# DC-DC.net
KiCad netlist of a schematic drawn in EAGLE
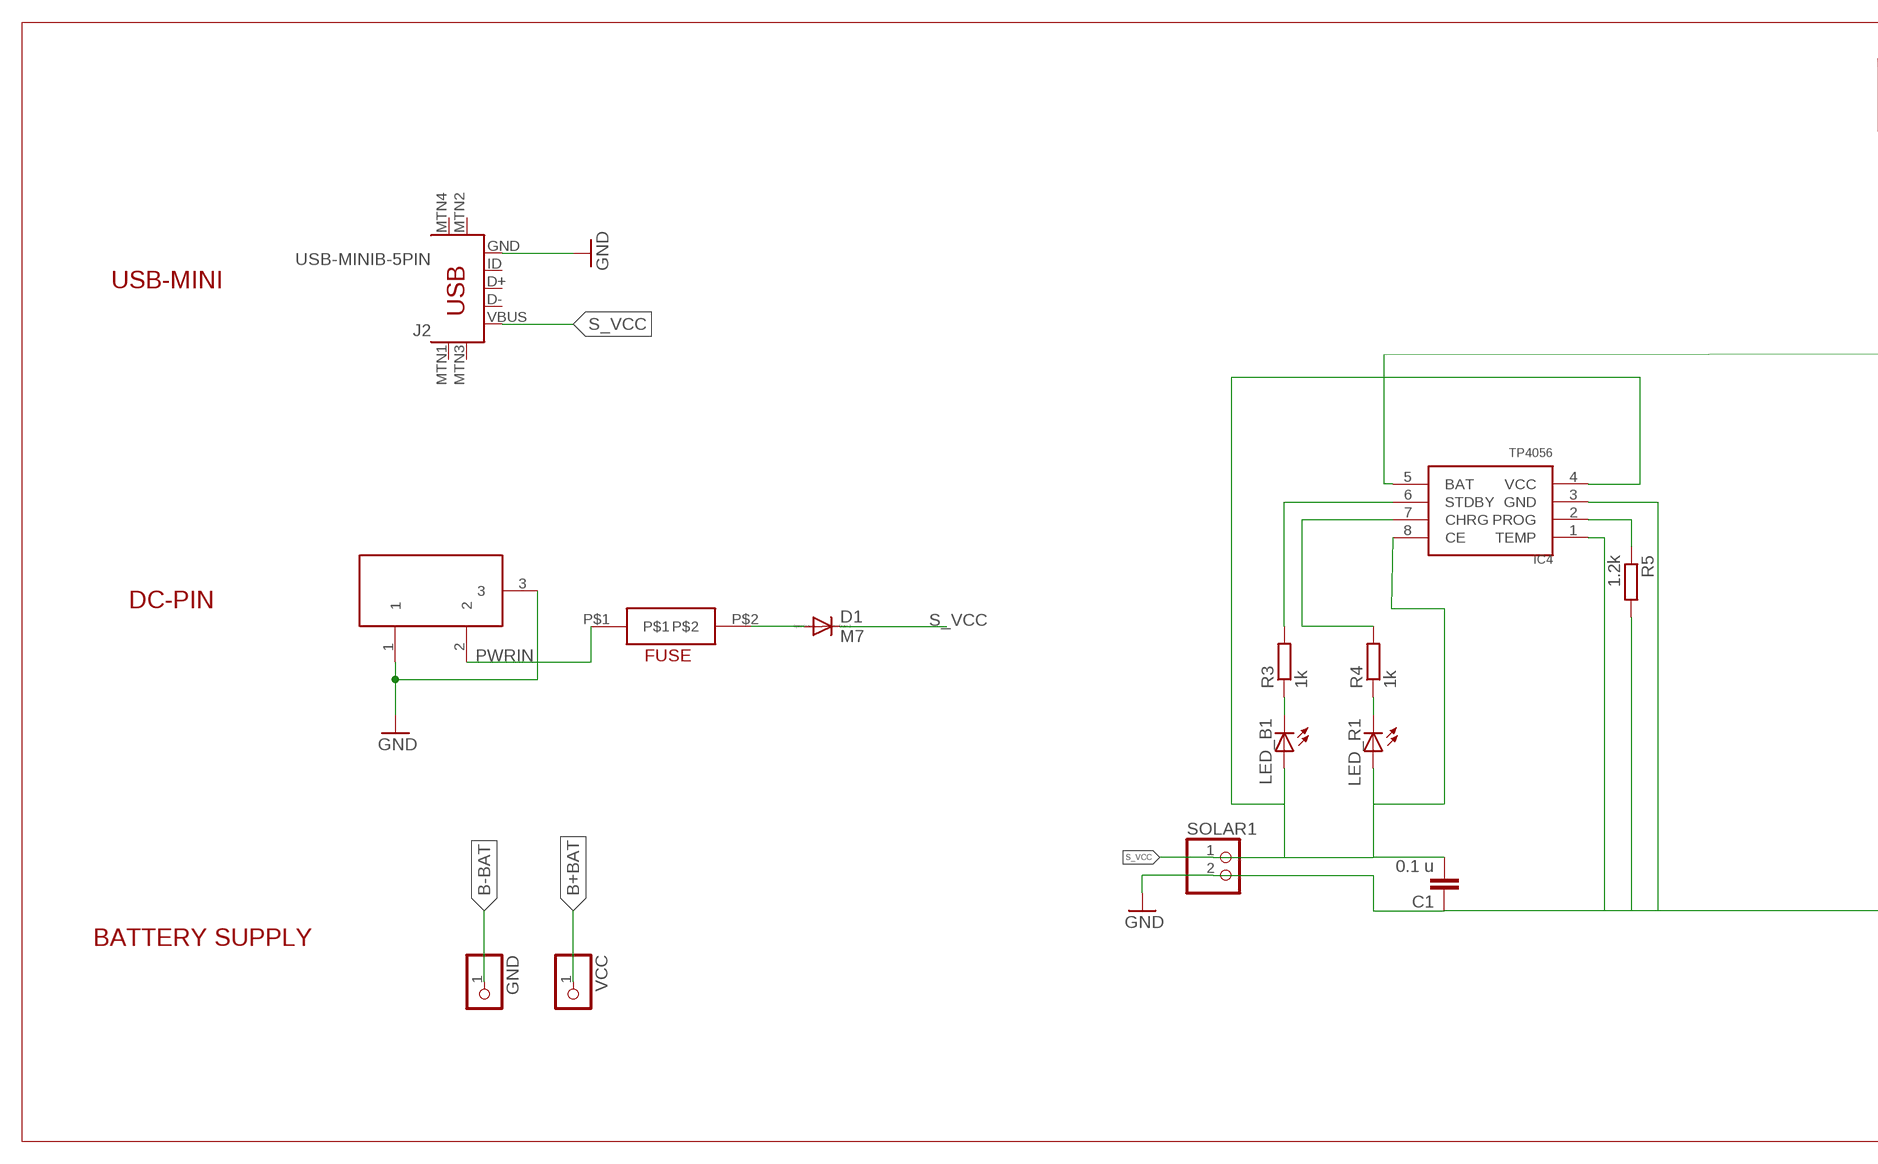
[diagram p0: schematic, sheet 1, part 1 of 2]
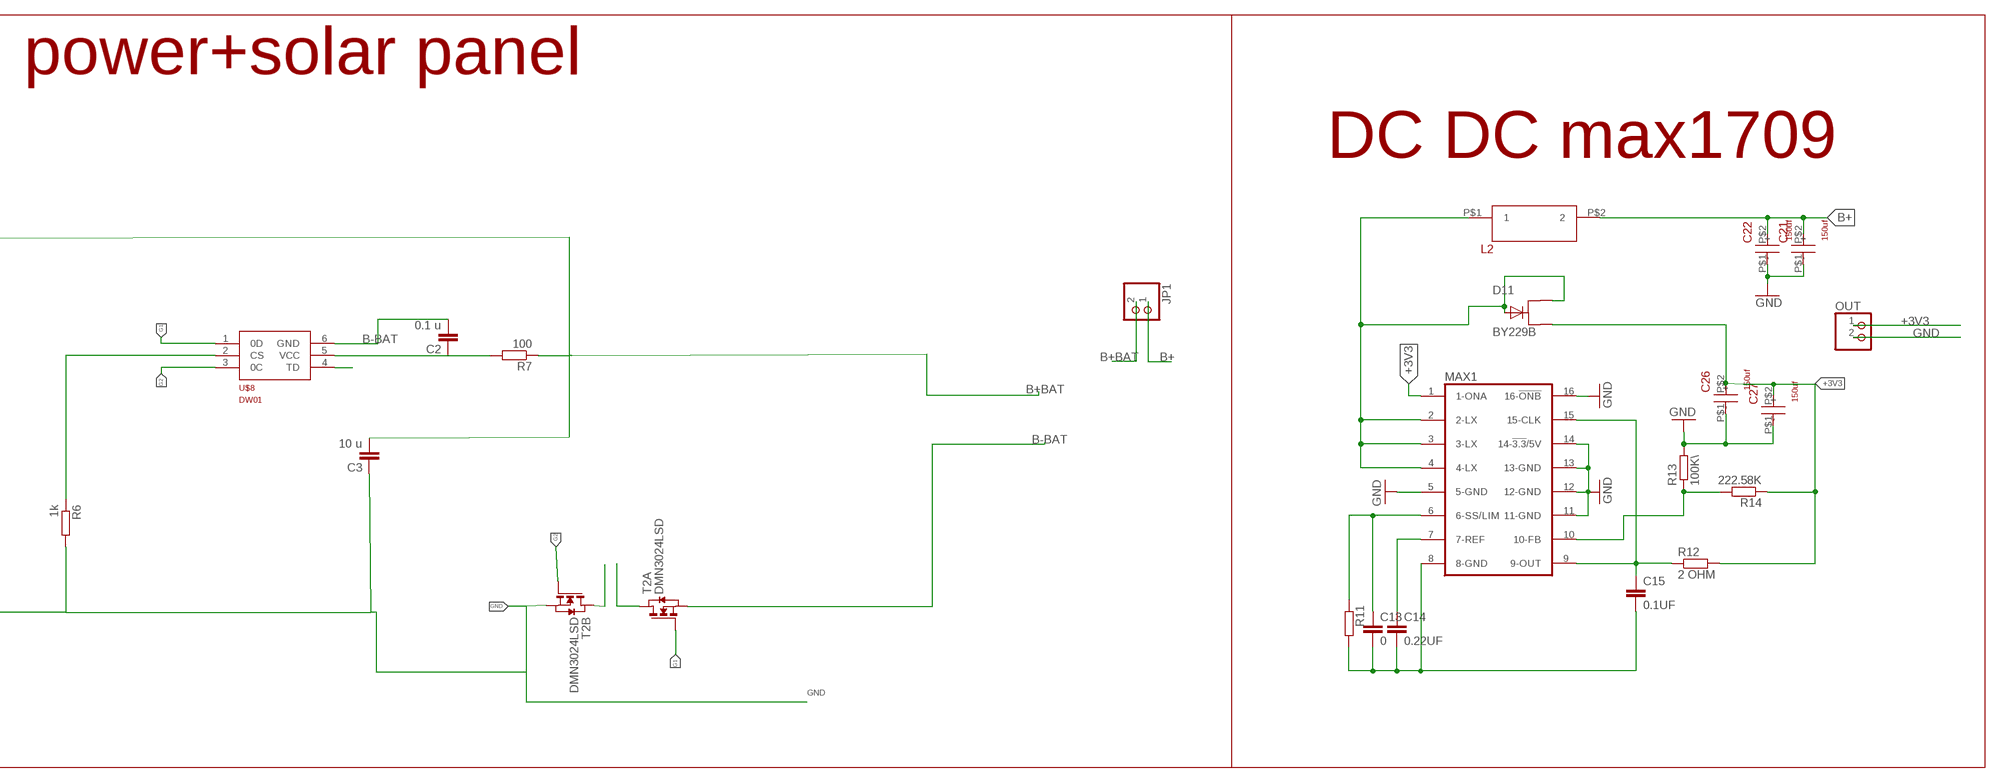
[diagram p1: schematic, sheet 1, part 2 of 2]

(export (version "E")
  (design (tool "Eeschema 10.0.6"))
  (components
    (comp (ref "C1")
      (value "0.1 u")
      (footprint "eagle-import:C0805")
      (libsource (lib "eagle-import") (part "C-EUC0805"))
    )
    (comp (ref "C2")
      (value "0.1 u")
      (footprint "eagle-import:C0805")
      (libsource (lib "eagle-import") (part "C-EUC0805"))
    )
    (comp (ref "C3")
      (value "10 u")
      (footprint "eagle-import:C0805")
      (libsource (lib "eagle-import") (part "C-EUC0805"))
    )
    (comp (ref "C13")
      (value "0")
      (footprint "eagle-import:C0805")
      (libsource (lib "eagle-import") (part "C-EUC0805"))
    )
    (comp (ref "C14")
      (value "0.22UF")
      (footprint "eagle-import:C0805")
      (libsource (lib "eagle-import") (part "C-EUC0805"))
    )
    (comp (ref "C15")
      (value "0.1UF")
      (footprint "eagle-import:C0805")
      (libsource (lib "eagle-import") (part "C-EUC0805"))
    )
    (comp (ref "C21")
      (value "150uf")
      (footprint "eagle-import:CAP")
      (libsource (lib "eagle-import") (part "MOSHE_CAP"))
    )
    (comp (ref "C22")
      (value "150uf")
      (footprint "eagle-import:CAP")
      (libsource (lib "eagle-import") (part "MOSHE_CAP"))
    )
    (comp (ref "C26")
      (value "150uf")
      (footprint "eagle-import:CAP")
      (libsource (lib "eagle-import") (part "MOSHE_CAP"))
    )
    (comp (ref "C27")
      (value "150uf")
      (footprint "eagle-import:CAP")
      (libsource (lib "eagle-import") (part "MOSHE_CAP"))
    )
    (comp (ref "D1")
      (value "M7")
      (footprint "eagle-import:SMB")
      (libsource (lib "eagle-import") (part "DIODE-SMB"))
    )
    (comp (ref "D11")
      (value "BY229B")
      (footprint "eagle-import:TO263AB")
      (libsource (lib "eagle-import") (part "BY229B"))
    )
    (comp (ref "GND")
      (value "PINHD-1X1")
      (footprint "eagle-import:1X01")
      (libsource (lib "eagle-import") (part "PINHD-1X1"))
    )
    (comp (ref "IC4")
      (value "TP4056")
      (footprint "eagle-import:SOP-8")
      (libsource (lib "eagle-import") (part "TP4056"))
    )
    (comp (ref "J2")
      (value "USB-MINIB-5PIN")
      (footprint "eagle-import:USB-MINIB")
      (libsource (lib "eagle-import") (part "USB-MINIB-5PIN"))
    )
    (comp (ref "JP1")
      (value "PINHD-1X2")
      (footprint "eagle-import:1X02")
      (libsource (lib "eagle-import") (part "PINHD-1X2"))
    )
    (comp (ref "L2")
      (value "INDUCTOR")
      (footprint "eagle-import:INDUCTOR_150")
      (libsource (lib "eagle-import") (part "INDUCTOR"))
    )
    (comp (ref "LED_B1")
      (value "LEDCHIP-LED0805")
      (footprint "eagle-import:CHIP-LED0805")
      (libsource (lib "eagle-import") (part "LEDCHIP-LED0805"))
    )
    (comp (ref "LED_R1")
      (value "LEDCHIP-LED0805")
      (footprint "eagle-import:CHIP-LED0805")
      (libsource (lib "eagle-import") (part "LEDCHIP-LED0805"))
    )
    (comp (ref "MAX1")
      (value "MOSHE_MAX1709F")
      (footprint "eagle-import:MAX1709")
      (libsource (lib "eagle-import") (part "MOSHE_MAX1709F"))
    )
    (comp (ref "OUT")
      (value "PINHD-1X2")
      (footprint "eagle-import:1X02")
      (libsource (lib "eagle-import") (part "PINHD-1X2"))
    )
    (comp (ref "R3")
      (value "1k")
      (footprint "eagle-import:R0805")
      (libsource (lib "eagle-import") (part "R-EU_R0805"))
    )
    (comp (ref "R4")
      (value "1k")
      (footprint "eagle-import:R0805")
      (libsource (lib "eagle-import") (part "R-EU_R0805"))
    )
    (comp (ref "R5")
      (value "1.2k")
      (footprint "eagle-import:R0805")
      (libsource (lib "eagle-import") (part "R-EU_R0805"))
    )
    (comp (ref "R6")
      (value "1k")
      (footprint "eagle-import:R0805")
      (libsource (lib "eagle-import") (part "R-EU_R0805"))
    )
    (comp (ref "R7")
      (value "100")
      (footprint "eagle-import:R0805")
      (libsource (lib "eagle-import") (part "R-EU_R0805"))
    )
    (comp (ref "R11")
      (value "R-EU_R0805")
      (footprint "eagle-import:R0805")
      (libsource (lib "eagle-import") (part "R-EU_R0805"))
    )
    (comp (ref "R12")
      (value "2 OHM")
      (footprint "eagle-import:R0805")
      (libsource (lib "eagle-import") (part "R-EU_R0805"))
    )
    (comp (ref "R13")
      (value "100K\\")
      (footprint "eagle-import:R0805")
      (libsource (lib "eagle-import") (part "R-EU_R0805"))
    )
    (comp (ref "R14")
      (value "222.58K")
      (footprint "eagle-import:R0805")
      (libsource (lib "eagle-import") (part "R-EU_R0805"))
    )
    (comp (ref "SOLAR1")
      (value "PINHD-1X2")
      (footprint "eagle-import:1X02")
      (libsource (lib "eagle-import") (part "PINHD-1X2"))
    )
    (comp (ref "T2")
      (value "DMN3024LSD")
      (footprint "eagle-import:TSSOP-8")
      (libsource (lib "eagle-import") (part "DMN3024LSD"))
    )
    (comp (ref "U$5")
      (value "FUSE_M")
      (footprint "eagle-import:DIP2")
      (libsource (lib "eagle-import") (part "FUSE_M"))
    )
    (comp (ref "U$8")
      (value "DW01")
      (footprint "eagle-import:SOT23-6")
      (libsource (lib "eagle-import") (part "DW01"))
    )
    (comp (ref "VCC")
      (value "PINHD-1X1")
      (footprint "eagle-import:1X01")
      (libsource (lib "eagle-import") (part "PINHD-1X1"))
    )
    (comp (ref "X1")
      (value "DC21MMX")
      (footprint "eagle-import:DC-21MM")
      (libsource (lib "eagle-import") (part "DC21MMX"))
    )
  )
  (nets
    (net (code "1") (name "+3V3") (class "Default")
      (node (ref "C26") (pin "P$2") (pinfunction "-_P$2") (pintype "bidirectional"))
      (node (ref "C27") (pin "P$2") (pinfunction "-_P$2") (pintype "bidirectional"))
      (node (ref "D11") (pin "K") (pinfunction "K_K") (pintype "passive"))
      (node (ref "MAX1") (pin "1") (pinfunction "1-ONA_1") (pintype "passive"))
      (node (ref "OUT") (pin "1") (pinfunction "1_1") (pintype "passive"))
      (node (ref "R12") (pin "2") (pinfunction "2_2") (pintype "passive"))
      (node (ref "R14") (pin "1") (pinfunction "1_1") (pintype "passive"))
    )
    (net (code "2") (name "/PWRIN") (class "Default")
      (node (ref "U$5") (pin "P$1") (pinfunction "P$1_P$1") (pintype "bidirectional"))
      (node (ref "X1") (pin "2") (pinfunction "2_2") (pintype "power_in"))
    )
    (net (code "3") (name "B+") (class "Default")
      (node (ref "C21") (pin "P$2") (pinfunction "-_P$2") (pintype "bidirectional"))
      (node (ref "C22") (pin "P$2") (pinfunction "-_P$2") (pintype "bidirectional"))
      (node (ref "JP1") (pin "1") (pinfunction "1_1") (pintype "passive"))
      (node (ref "L2") (pin "P$2") (pinfunction "2_P$2") (pintype "bidirectional"))
    )
    (net (code "4") (name "B+BAT") (class "Default")
      (node (ref "C3") (pin "2") (pinfunction "2_2") (pintype "passive"))
      (node (ref "IC4") (pin "5") (pinfunction "BAT_5") (pintype "bidirectional"))
      (node (ref "JP1") (pin "2") (pinfunction "2_2") (pintype "passive"))
      (node (ref "R7") (pin "1") (pinfunction "1_1") (pintype "passive"))
      (node (ref "VCC") (pin "1") (pinfunction "1_1") (pintype "passive"))
    )
    (net (code "5") (name "B-BAT") (class "Default")
      (node (ref "C2") (pin "2") (pinfunction "2_2") (pintype "passive"))
      (node (ref "GND") (pin "1") (pinfunction "1_1") (pintype "passive"))
      (node (ref "T2") (pin "2") (pinfunction "S_2") (pintype "passive"))
      (node (ref "T2") (pin "3") (pinfunction "S_3") (pintype "passive"))
      (node (ref "U$8") (pin "6") (pinfunction "GND_6") (pintype "bidirectional"))
    )
    (net (code "6") (name "G1") (class "Default")
      (node (ref "T2") (pin "4") (pinfunction "G_4") (pintype "passive"))
      (node (ref "U$8") (pin "1") (pinfunction "0D_1") (pintype "bidirectional"))
    )
    (net (code "7") (name "G2") (class "Default")
      (node (ref "T2") (pin "5") (pinfunction "G_5") (pintype "passive"))
      (node (ref "U$8") (pin "3") (pinfunction "0C_3") (pintype "bidirectional"))
    )
    (net (code "8") (name "GND") (class "Default")
      (node (ref "C1") (pin "1") (pinfunction "1_1") (pintype "passive"))
      (node (ref "C13") (pin "2") (pinfunction "2_2") (pintype "passive"))
      (node (ref "C14") (pin "2") (pinfunction "2_2") (pintype "passive"))
      (node (ref "C15") (pin "2") (pinfunction "2_2") (pintype "passive"))
      (node (ref "C21") (pin "P$1") (pinfunction "+_P$1") (pintype "bidirectional"))
      (node (ref "C22") (pin "P$1") (pinfunction "+_P$1") (pintype "bidirectional"))
      (node (ref "C26") (pin "P$1") (pinfunction "+_P$1") (pintype "bidirectional"))
      (node (ref "C27") (pin "P$1") (pinfunction "+_P$1") (pintype "bidirectional"))
      (node (ref "C3") (pin "1") (pinfunction "1_1") (pintype "passive"))
      (node (ref "IC4") (pin "1") (pinfunction "TEMP_1") (pintype "bidirectional"))
      (node (ref "IC4") (pin "3") (pinfunction "GND_3") (pintype "bidirectional"))
      (node (ref "J2") (pin "GND") (pinfunction "GND_GND") (pintype "bidirectional"))
      (node (ref "MAX1") (pin "11") (pinfunction "11-GND_11") (pintype "input"))
      (node (ref "MAX1") (pin "12") (pinfunction "12-GND_12") (pintype "input"))
      (node (ref "MAX1") (pin "13") (pinfunction "13-GND_13") (pintype "power_in"))
      (node (ref "MAX1") (pin "14") (pinfunction "14-~{3.3}/5V_14") (pintype "power_in"))
      (node (ref "MAX1") (pin "16") (pinfunction "16-~{ONB}_16") (pintype "passive"))
      (node (ref "MAX1") (pin "5") (pinfunction "5-GND_5") (pintype "passive"))
      (node (ref "MAX1") (pin "8") (pinfunction "8-GND_8") (pintype "passive"))
      (node (ref "OUT") (pin "2") (pinfunction "2_2") (pintype "passive"))
      (node (ref "R11") (pin "2") (pinfunction "2_2") (pintype "passive"))
      (node (ref "R13") (pin "2") (pinfunction "2_2") (pintype "passive"))
      (node (ref "R5") (pin "2") (pinfunction "2_2") (pintype "passive"))
      (node (ref "R6") (pin "2") (pinfunction "2_2") (pintype "passive"))
      (node (ref "SOLAR1") (pin "2") (pinfunction "2_2") (pintype "passive"))
      (node (ref "T2") (pin "6") (pinfunction "S_6") (pintype "passive"))
      (node (ref "T2") (pin "7") (pinfunction "S_7") (pintype "passive"))
      (node (ref "X1") (pin "1") (pinfunction "1_1") (pintype "power_in"))
      (node (ref "X1") (pin "3") (pinfunction "3_3") (pintype "power_in"))
    )
    (net (code "9") (name "Net-(D1-PadA)") (class "Default")
      (node (ref "D1") (pin "A") (pinfunction "A_A") (pintype "passive"))
      (node (ref "U$5") (pin "P$2") (pinfunction "P$2_P$2") (pintype "bidirectional"))
    )
    (net (code "10") (name "Net-(IC4-CHRG)") (class "Default")
      (node (ref "IC4") (pin "7") (pinfunction "CHRG_7") (pintype "bidirectional"))
      (node (ref "R4") (pin "2") (pinfunction "2_2") (pintype "passive"))
    )
    (net (code "11") (name "Net-(IC4-PROG)") (class "Default")
      (node (ref "IC4") (pin "2") (pinfunction "PROG_2") (pintype "bidirectional"))
      (node (ref "R5") (pin "1") (pinfunction "1_1") (pintype "passive"))
    )
    (net (code "12") (name "Net-(IC4-STDBY)") (class "Default")
      (node (ref "IC4") (pin "6") (pinfunction "STDBY_6") (pintype "bidirectional"))
      (node (ref "R3") (pin "2") (pinfunction "2_2") (pintype "passive"))
    )
    (net (code "13") (name "Net-(L2-1)") (class "Default")
      (node (ref "D11") (pin "1") (pinfunction "1_1") (pintype "passive"))
      (node (ref "D11") (pin "2") (pinfunction "2_2") (pintype "passive"))
      (node (ref "L2") (pin "P$1") (pinfunction "1_P$1") (pintype "bidirectional"))
      (node (ref "MAX1") (pin "2") (pinfunction "2-LX_2") (pintype "passive"))
      (node (ref "MAX1") (pin "3") (pinfunction "3-LX_3") (pintype "passive"))
      (node (ref "MAX1") (pin "4") (pinfunction "4-LX_4") (pintype "passive"))
    )
    (net (code "14") (name "Net-(LED_B1-PadC)") (class "Default")
      (node (ref "LED_B1") (pin "C") (pinfunction "C_C") (pintype "passive"))
      (node (ref "R3") (pin "1") (pinfunction "1_1") (pintype "passive"))
    )
    (net (code "15") (name "Net-(LED_R1-PadC)") (class "Default")
      (node (ref "LED_R1") (pin "C") (pinfunction "C_C") (pintype "passive"))
      (node (ref "R4") (pin "1") (pinfunction "1_1") (pintype "passive"))
    )
    (net (code "16") (name "Net-(MAX1-6-SS{slash}LIM)") (class "Default")
      (node (ref "C13") (pin "1") (pinfunction "1_1") (pintype "passive"))
      (node (ref "MAX1") (pin "6") (pinfunction "6-SS/LIM_6") (pintype "passive"))
      (node (ref "R11") (pin "1") (pinfunction "1_1") (pintype "passive"))
    )
    (net (code "17") (name "Net-(MAX1-7-REF)") (class "Default")
      (node (ref "C14") (pin "1") (pinfunction "1_1") (pintype "passive"))
      (node (ref "MAX1") (pin "7") (pinfunction "7-REF_7") (pintype "passive"))
    )
    (net (code "18") (name "Net-(MAX1-10-FB)") (class "Default")
      (node (ref "MAX1") (pin "10") (pinfunction "10-FB_10") (pintype "input"))
      (node (ref "R13") (pin "1") (pinfunction "1_1") (pintype "passive"))
      (node (ref "R14") (pin "2") (pinfunction "2_2") (pintype "passive"))
    )
    (net (code "19") (name "Net-(MAX1-15-CLK)") (class "Default")
      (node (ref "C15") (pin "1") (pinfunction "1_1") (pintype "passive"))
      (node (ref "MAX1") (pin "15") (pinfunction "15-CLK_15") (pintype "power_in"))
      (node (ref "MAX1") (pin "9") (pinfunction "9-OUT_9") (pintype "input"))
      (node (ref "R12") (pin "1") (pinfunction "1_1") (pintype "passive"))
    )
    (net (code "20") (name "Net-(U$8-CS)") (class "Default")
      (node (ref "R6") (pin "1") (pinfunction "1_1") (pintype "passive"))
      (node (ref "U$8") (pin "2") (pinfunction "CS_2") (pintype "bidirectional"))
    )
    (net (code "21") (name "Net-(U$8-VCC)") (class "Default")
      (node (ref "C2") (pin "1") (pinfunction "1_1") (pintype "passive"))
      (node (ref "R7") (pin "2") (pinfunction "2_2") (pintype "passive"))
      (node (ref "U$8") (pin "5") (pinfunction "VCC_5") (pintype "bidirectional"))
    )
    (net (code "22") (name "S_VCC") (class "Default")
      (node (ref "C1") (pin "2") (pinfunction "2_2") (pintype "passive"))
      (node (ref "D1") (pin "C") (pinfunction "C_C") (pintype "passive"))
      (node (ref "IC4") (pin "4") (pinfunction "VCC_4") (pintype "bidirectional"))
      (node (ref "IC4") (pin "8") (pinfunction "CE_8") (pintype "bidirectional"))
      (node (ref "J2") (pin "VBUS") (pinfunction "VBUS_VBUS") (pintype "bidirectional"))
      (node (ref "LED_B1") (pin "A") (pinfunction "A_A") (pintype "passive"))
      (node (ref "LED_R1") (pin "A") (pinfunction "A_A") (pintype "passive"))
      (node (ref "SOLAR1") (pin "1") (pinfunction "1_1") (pintype "passive"))
    )
    (net (code "23") (name "unconnected-(J2-MTN1-PadMTN3)") (class "Default")
      (node (ref "J2") (pin "MTN3") (pinfunction "MTN1_MTN3") (pintype "bidirectional"))
    )
    (net (code "24") (name "unconnected-(J2-MTN2-PadMTN1)") (class "Default")
      (node (ref "J2") (pin "MTN1") (pinfunction "MTN2_MTN1") (pintype "bidirectional"))
    )
    (net (code "25") (name "unconnected-(J2-MTN3-PadMTN2)") (class "Default")
      (node (ref "J2") (pin "MTN2") (pinfunction "MTN3_MTN2") (pintype "bidirectional"))
    )
    (net (code "26") (name "unconnected-(J2-PadD+)") (class "Default")
      (node (ref "J2") (pin "D+") (pinfunction "D+_D+") (pintype "bidirectional"))
    )
    (net (code "27") (name "unconnected-(J2-PadD-)") (class "Default")
      (node (ref "J2") (pin "D-") (pinfunction "D-_D-") (pintype "bidirectional"))
    )
    (net (code "28") (name "unconnected-(J2-PadID)") (class "Default")
      (node (ref "J2") (pin "ID") (pinfunction "ID_ID") (pintype "bidirectional"))
    )
    (net (code "29") (name "unconnected-(J2-PadMTN4)") (class "Default")
      (node (ref "J2") (pin "MTN4") (pinfunction "MTN4_MTN4") (pintype "bidirectional"))
    )
    (net (code "30") (name "unconnected-(T2A-D-Pad1)") (class "Default")
      (node (ref "T2") (pin "1") (pinfunction "D_1") (pintype "passive"))
    )
    (net (code "31") (name "unconnected-(T2B-D-Pad8)") (class "Default")
      (node (ref "T2") (pin "8") (pinfunction "D_8") (pintype "passive"))
    )
    (net (code "32") (name "unconnected-(U$8-TD-Pad4)") (class "Default")
      (node (ref "U$8") (pin "4") (pinfunction "TD_4") (pintype "bidirectional"))
    )
  )
)
